# SerialCommunication1.net
KiCad netlist of a schematic drawn in Altium Designer
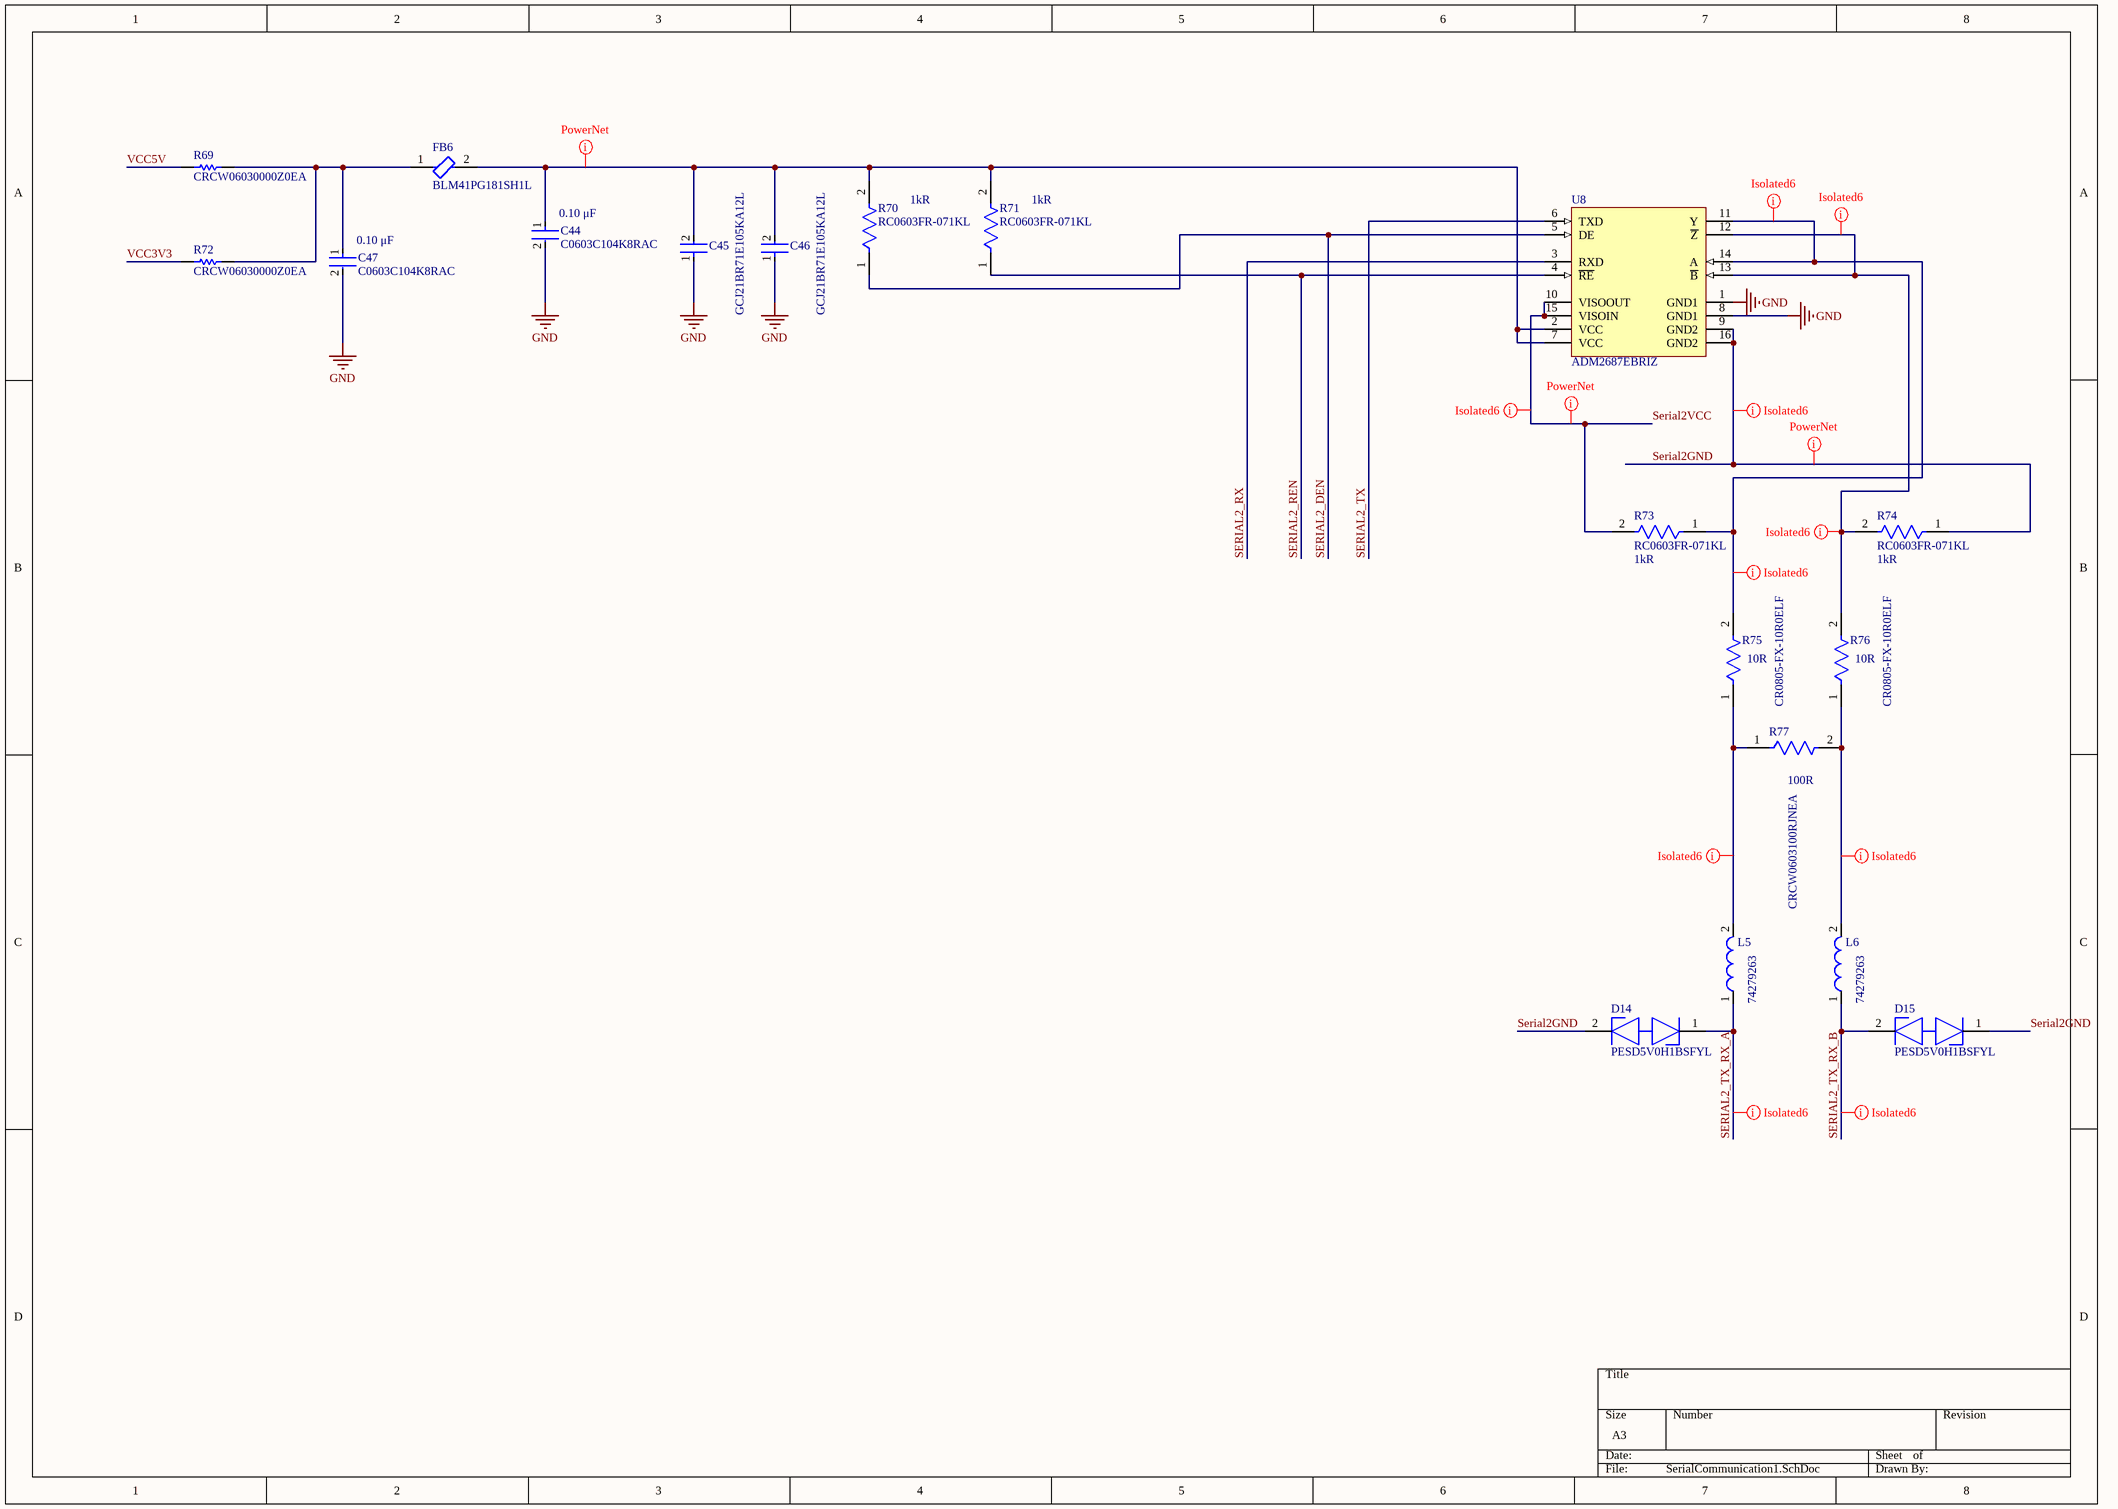
[diagram p0: SerialCommunication1.SchDoc]

(export (version "E")
  (design (tool "Eeschema 10.0.6"))
  (components
    (comp (ref "C44")
      (value "C0603C104K8RAC")
      (footprint "FP-C0603C-CF-MFG")
      (description "C0603 0.10 μF X7R 30ppm/°C 10.00% 10 V")
      (fields
        (field (name "MANUFACTURER") "KEMET")
        (field (name "CAPACITANCE") "0.10 μF")
        (field (name "OCTOPART") "https://octopart.com/c0603c104k8rac-kemet-1325403")
      )
      (libsource (lib "Altium Content Vault") (part "b4654b650e69147ec39a6b967a45e02"))
    )
    (comp (ref "C45")
      (value "GCJ21BR71E105KA12L")
      (footprint "FP-GCJ21B-0_3-MFG")
      (description "Multilayer Ceramic Capacitors MLCC - SMD/SMT 0805 1uF 10%, 25VDC,  X7R 15%")
      (fields (field (name "TOLERANCE") "10%"))
      (libsource (lib "Altium Content Vault") (part "02cd4be3c70576c341d710602a673aa"))
    )
    (comp (ref "C46")
      (value "GCJ21BR71E105KA12L")
      (footprint "FP-GCJ21B-0_3-MFG")
      (description "Multilayer Ceramic Capacitors MLCC - SMD/SMT 0805 1uF 10%, 25VDC,  X7R 15%")
      (fields (field (name "TOLERANCE") "10%"))
      (libsource (lib "Altium Content Vault") (part "02cd4be3c70576c341d710602a673aa"))
    )
    (comp (ref "C47")
      (value "C0603C104K8RAC")
      (footprint "FP-C0603C-CF-MFG")
      (description "C0603 0.10 μF X7R 30ppm/°C 10.00% 10 V")
      (fields
        (field (name "MANUFACTURER") "KEMET")
        (field (name "CAPACITANCE") "0.10 μF")
        (field (name "OCTOPART") "https://octopart.com/c0603c104k8rac-kemet-1325403")
      )
      (libsource (lib "Altium Content Vault") (part "b4654b650e69147ec39a6b967a45e02"))
    )
    (comp (ref "D14")
      (value "PESD5V0H1BSFYL")
      (footprint "FP-SOD962-2-MFG")
      (description "TVS DIODE 5V 5V DSN0603-2")
      (fields
        (field (name "OCTOPART") "https://octopart.com/pesd5v0h1bsfyl-nexperia-78741149")
        (field (name "MANUFACTURER") "Nexperia")
      )
      (libsource (lib "Altium Content Vault") (part "35d3c4067516f6c39e60198d779250f"))
    )
    (comp (ref "D15")
      (value "PESD5V0H1BSFYL")
      (footprint "FP-SOD962-2-MFG")
      (description "TVS DIODE 5V 5V DSN0603-2")
      (fields
        (field (name "OCTOPART") "https://octopart.com/pesd5v0h1bsfyl-nexperia-78741149")
        (field (name "MANUFACTURER") "Nexperia")
      )
      (libsource (lib "Altium Content Vault") (part "35d3c4067516f6c39e60198d779250f"))
    )
    (comp (ref "FB6")
      (value "BLM41PG181SH1L")
      (footprint "FP-BLM41-0_2-a1_2-MFG")
      (description "Ferrite Bead, 1806, 180Ω @ 100MHz, 25%, 0.02Ω, 3.5A")
      (fields (field (name "TOLERANCE") "25%"))
      (libsource (lib "Altium Content Vault") (part "5f30dd21d616792df468990f7003faa"))
    )
    (comp (ref "L5")
      (value "74279263")
      (footprint "SMD-0603")
      (description "SMD EMI Suppression Ferrite Bead WE-CBF, Z = 220 Ohm")
      (libsource (lib "Altium Content Vault") (part "PAS-IND-INDUCTOR-2"))
    )
    (comp (ref "L6")
      (value "74279263")
      (footprint "SMD-0603")
      (description "SMD EMI Suppression Ferrite Bead WE-CBF, Z = 220 Ohm")
      (libsource (lib "Altium Content Vault") (part "PAS-IND-INDUCTOR-2"))
    )
    (comp (ref "R69")
      (value "CRCW06030000Z0EA")
      (footprint "RESC1609X50X30NL8T20")
      (description "Chip Resistor, 0 Ohm, Jumper, 100 mW, -55 to 155 degC, 0603 (1608 Metric), RoHS, Tape and Reel")
      (fields (field (name "MANUFACTURER") "Vishay Semiconductor"))
      (libsource (lib "Altium Content Vault") (part "RES-2"))
    )
    (comp (ref "R70")
      (value "RC0603FR-071KL")
      (footprint "FP-RC0603-0_55-IPC_C")
      (description "RES 1K OHM 1% 1/10W 0603")
      (fields (field (name "RESISTANCE") "1kR") (field (name "TOLERANCE") "1%"))
      (libsource (lib "Altium Content Vault") (part "1029c3af85768c4190bb7ad29bc67b5"))
    )
    (comp (ref "R71")
      (value "RC0603FR-071KL")
      (footprint "FP-RC0603-0_55-IPC_C")
      (description "RES 1K OHM 1% 1/10W 0603")
      (fields (field (name "RESISTANCE") "1kR") (field (name "TOLERANCE") "1%"))
      (libsource (lib "Altium Content Vault") (part "1029c3af85768c4190bb7ad29bc67b5"))
    )
    (comp (ref "R72")
      (value "CRCW06030000Z0EA")
      (footprint "RESC1609X50X30NL8T20")
      (description "Chip Resistor, 0 Ohm, Jumper, 100 mW, -55 to 155 degC, 0603 (1608 Metric), RoHS, Tape and Reel")
      (fields (field (name "MANUFACTURER") "Vishay Semiconductor"))
      (libsource (lib "Altium Content Vault") (part "RES-2"))
    )
    (comp (ref "R73")
      (value "RC0603FR-071KL")
      (footprint "FP-RC0603-0_55-IPC_C")
      (description "RES 1K OHM 1% 1/10W 0603")
      (fields (field (name "RESISTANCE") "1kR") (field (name "TOLERANCE") "1%"))
      (libsource (lib "Altium Content Vault") (part "1029c3af85768c4190bb7ad29bc67b5"))
    )
    (comp (ref "R74")
      (value "RC0603FR-071KL")
      (footprint "FP-RC0603-0_55-IPC_C")
      (description "RES 1K OHM 1% 1/10W 0603")
      (fields (field (name "RESISTANCE") "1kR") (field (name "TOLERANCE") "1%"))
      (libsource (lib "Altium Content Vault") (part "1029c3af85768c4190bb7ad29bc67b5"))
    )
    (comp (ref "R75")
      (value "CR0805-FX-10R0ELF")
      (footprint "FP-CR0805-IPC_B")
      (description "Thick Film Chip Resistors 0805 10Ω 0.125W 1% 100ppm/°C")
      (fields (field (name "TOLERANCE") "1%") (field (name "RESISTANCE") "10R"))
      (libsource (lib "Altium Content Vault") (part "1029c3af85768c4190bb7ad29bc67b5"))
    )
    (comp (ref "R76")
      (value "CR0805-FX-10R0ELF")
      (footprint "FP-CR0805-IPC_B")
      (description "Thick Film Chip Resistors 0805 10Ω 0.125W 1% 100ppm/°C")
      (fields (field (name "TOLERANCE") "1%") (field (name "RESISTANCE") "10R"))
      (libsource (lib "Altium Content Vault") (part "1029c3af85768c4190bb7ad29bc67b5"))
    )
    (comp (ref "R77")
      (value "CRCW0603100RJNEA")
      (footprint "FP-CRCW0603-e3-IPC_B")
      (description "RES Thick Film, 100Ω, 5%, 0.1W, 200ppm/°C, 0603")
      (fields (field (name "RESISTANCE") "100R") (field (name "TOLERANCE") "5%"))
      (libsource (lib "Altium Content Vault") (part "1029c3af85768c4190bb7ad29bc67b5"))
    )
    (comp (ref "U8")
      (value "ADM2687EBRIZ")
      (footprint "ADI-RI-16-2_L")
      (fields (field (name "MANUFACTURER") "Analog Devices"))
      (libsource (lib "Altium Content Vault") (part "ADI-ADM268X-RI-16-2"))
    )
  )
  (nets
    (net (code "1") (name "/SERIAL2_DEN") (class "Default")
      (node (ref "R70") (pin "1") (pinfunction "1_1") (pintype "passive"))
      (node (ref "U8") (pin "5") (pinfunction "DE_5") (pintype "input"))
    )
    (net (code "2") (name "/SERIAL2_REN") (class "Default")
      (node (ref "R71") (pin "1") (pinfunction "1_1") (pintype "passive"))
      (node (ref "U8") (pin "4") (pinfunction "~{RE}_4") (pintype "input"))
    )
    (net (code "3") (name "/SERIAL2_RX") (class "Default")
      (node (ref "U8") (pin "3") (pinfunction "RXD_3") (pintype "tri_state"))
    )
    (net (code "4") (name "/SERIAL2_TX") (class "Default")
      (node (ref "U8") (pin "6") (pinfunction "TXD_6") (pintype "input"))
    )
    (net (code "5") (name "/SERIAL2_TX_RX_A") (class "Default")
      (node (ref "D14") (pin "1") (pinfunction "K1_1") (pintype "passive"))
      (node (ref "L5") (pin "1") (pinfunction "1_1") (pintype "passive"))
    )
    (net (code "6") (name "/SERIAL2_TX_RX_B") (class "Default")
      (node (ref "D15") (pin "2") (pinfunction "K2_2") (pintype "passive"))
      (node (ref "L6") (pin "1") (pinfunction "1_1") (pintype "passive"))
    )
    (net (code "7") (name "/Serial2GND") (class "Default")
      (node (ref "D14") (pin "2") (pinfunction "K2_2") (pintype "passive"))
      (node (ref "D15") (pin "1") (pinfunction "K1_1") (pintype "passive"))
      (node (ref "R74") (pin "1") (pinfunction "1_1") (pintype "passive"))
      (node (ref "U8") (pin "16") (pinfunction "GND2_16") (pintype "power_in"))
      (node (ref "U8") (pin "9") (pinfunction "GND2_9") (pintype "power_in"))
    )
    (net (code "8") (name "/Serial2VCC") (class "Default")
      (node (ref "R73") (pin "2") (pinfunction "2_2") (pintype "passive"))
      (node (ref "U8") (pin "10") (pinfunction "VISOOUT_10") (pintype "power_in"))
      (node (ref "U8") (pin "15") (pinfunction "VISOIN_15") (pintype "power_in"))
    )
    (net (code "9") (name "/VCC3V3") (class "Default")
      (node (ref "R72") (pin "1") (pinfunction "1_1") (pintype "passive"))
    )
    (net (code "10") (name "/VCC5V") (class "Default")
      (node (ref "R69") (pin "1") (pinfunction "1_1") (pintype "passive"))
    )
    (net (code "11") (name "GND") (class "Default")
      (node (ref "C44") (pin "2") (pinfunction "2_2") (pintype "passive"))
      (node (ref "C45") (pin "1") (pinfunction "1_1") (pintype "passive"))
      (node (ref "C46") (pin "1") (pinfunction "1_1") (pintype "passive"))
      (node (ref "C47") (pin "2") (pinfunction "2_2") (pintype "passive"))
      (node (ref "U8") (pin "1") (pinfunction "GND1_1") (pintype "power_in"))
      (node (ref "U8") (pin "8") (pinfunction "GND1_8") (pintype "power_in"))
    )
    (net (code "12") (name "Net-(C44-Pad1)") (class "Default")
      (node (ref "C44") (pin "1") (pinfunction "1_1") (pintype "passive"))
      (node (ref "C45") (pin "2") (pinfunction "2_2") (pintype "passive"))
      (node (ref "C46") (pin "2") (pinfunction "2_2") (pintype "passive"))
      (node (ref "FB6") (pin "2") (pinfunction "2_2") (pintype "passive"))
      (node (ref "R70") (pin "2") (pinfunction "2_2") (pintype "passive"))
      (node (ref "R71") (pin "2") (pinfunction "2_2") (pintype "passive"))
      (node (ref "U8") (pin "2") (pinfunction "VCC_2") (pintype "power_in"))
      (node (ref "U8") (pin "7") (pinfunction "VCC_7") (pintype "power_in"))
    )
    (net (code "13") (name "Net-(C47-Pad1)") (class "Default")
      (node (ref "C47") (pin "1") (pinfunction "1_1") (pintype "passive"))
      (node (ref "FB6") (pin "1") (pinfunction "1_1") (pintype "passive"))
      (node (ref "R69") (pin "2") (pinfunction "2_2") (pintype "passive"))
      (node (ref "R72") (pin "2") (pinfunction "2_2") (pintype "passive"))
    )
    (net (code "14") (name "Net-(L5-Pad2)") (class "Default")
      (node (ref "L5") (pin "2") (pinfunction "2_2") (pintype "passive"))
      (node (ref "R75") (pin "1") (pinfunction "1_1") (pintype "passive"))
      (node (ref "R77") (pin "1") (pinfunction "1_1") (pintype "passive"))
    )
    (net (code "15") (name "Net-(L6-Pad2)") (class "Default")
      (node (ref "L6") (pin "2") (pinfunction "2_2") (pintype "passive"))
      (node (ref "R76") (pin "1") (pinfunction "1_1") (pintype "passive"))
      (node (ref "R77") (pin "2") (pinfunction "2_2") (pintype "passive"))
    )
    (net (code "16") (name "Net-(U8-A)") (class "Default")
      (node (ref "R73") (pin "1") (pinfunction "1_1") (pintype "passive"))
      (node (ref "R75") (pin "2") (pinfunction "2_2") (pintype "passive"))
      (node (ref "U8") (pin "11") (pinfunction "Y_11") (pintype "tri_state"))
      (node (ref "U8") (pin "14") (pinfunction "A_14") (pintype "input"))
    )
    (net (code "17") (name "Net-(U8-~{B})") (class "Default")
      (node (ref "R74") (pin "2") (pinfunction "2_2") (pintype "passive"))
      (node (ref "R76") (pin "2") (pinfunction "2_2") (pintype "passive"))
      (node (ref "U8") (pin "12") (pinfunction "~{Z}_12") (pintype "tri_state"))
      (node (ref "U8") (pin "13") (pinfunction "~{B}_13") (pintype "input"))
    )
  )
)
